# BTN2_FactoryReset.net
KiCad netlist of a schematic drawn in Altium Designer
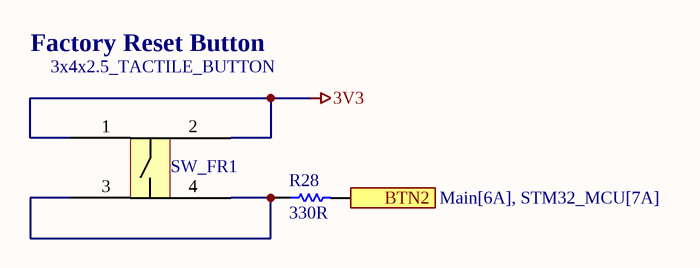
[diagram p0: BTN2_FactoryReset.SchDoc]

(export (version "E")
  (design (tool "Eeschema 10.0.6"))
  (components
    (comp (ref "R28")
      (value "330R")
      (footprint "RESC1608X55X30LL15T15")
      (description "Chip Resistor, 330 Ohm, +/- 1%, 0.1 W, -55 to 155 degC, 0603 (1608 Metric), RoHS, Tape and Reel")
      (libsource (lib "Altium Content Vault") (part "RES-2"))
    )
    (comp (ref "SW_FR1")
      (value "3x4x2.5_TACTILE_BUTTON")
      (footprint "3x4x2.5_TACTILE_BUTTON")
      (libsource (lib "3x4x2.5_TACTILE_BUTTON") (part "3x4x2.5_TACTILE_BUTTON"))
    )
  )
  (nets
    (net (code "1") (name "/BTN2") (class "Default")
      (node (ref "R28") (pin "2") (pinfunction "2_2") (pintype "passive"))
    )
    (net (code "2") (name "3V3") (class "Default")
      (node (ref "SW_FR1") (pin "1") (pinfunction "1_1") (pintype "passive"))
      (node (ref "SW_FR1") (pin "2") (pinfunction "2_2") (pintype "passive"))
    )
    (net (code "3") (name "Net-(R28-Pad1)") (class "Default")
      (node (ref "R28") (pin "1") (pinfunction "1_1") (pintype "passive"))
      (node (ref "SW_FR1") (pin "3") (pinfunction "3_3") (pintype "passive"))
      (node (ref "SW_FR1") (pin "4") (pinfunction "4_4") (pintype "passive"))
    )
  )
)
